# USB_Serial.net
KiCad netlist of a schematic drawn in Altium Designer
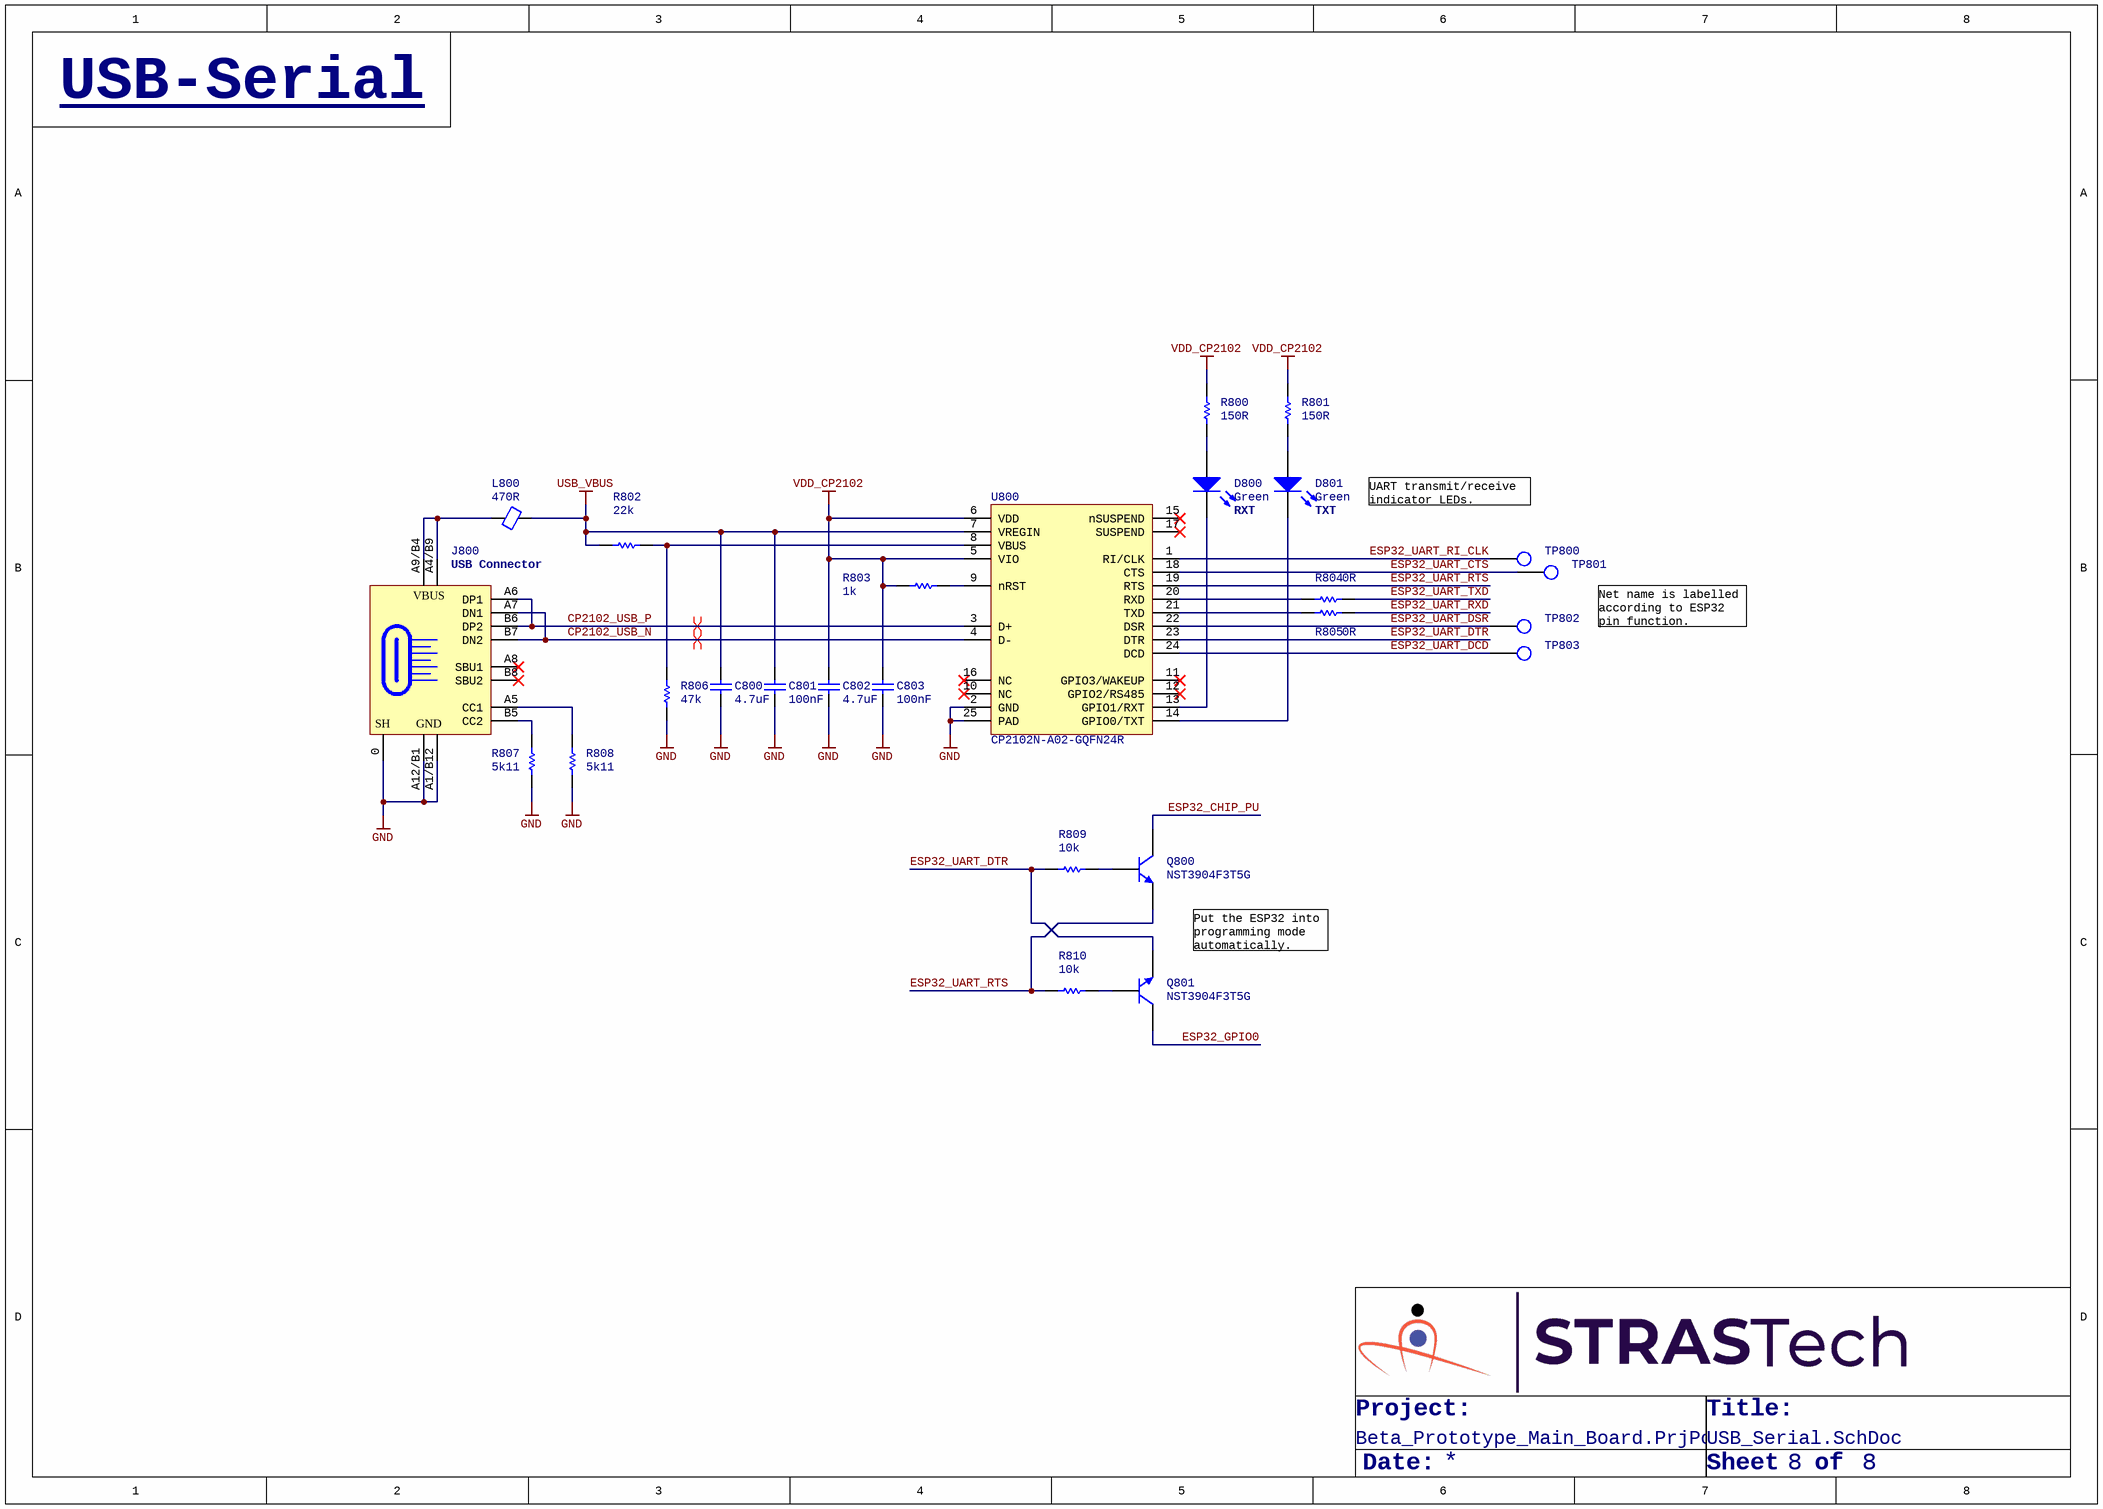
[diagram p0: USB_Serial.SchDoc]

(export (version "E")
  (design (tool "Eeschema 10.0.6"))
  (components
    (comp (ref "C800")
      (value "4.7uF")
      (footprint "Cap,SMD,0402")
      (description "4.7 µF ±20% 16V Ceramic Capacitor X5R 0402 (1005 Metric)")
      (fields
        (field (name "VENDOR PART NUMBER") "478-10788-1-ND")
        (field (name "MANUFACTURER") "AVX Corporation")
        (field (name "CREATEDBY") "Judd Foster")
      )
      (libsource (lib "symbols") (part "CAP,Cer,4.7uF,16VDC,X5R,0402"))
    )
    (comp (ref "C801")
      (value "100nF")
      (footprint "Cap,SMD,0402")
      (description "0.1µF ±10% 25V Ceramic Capacitor X7R 0402 (1005 Metric)")
      (fields
        (field (name "VENDOR PART NUMBER") "490-14603-1-ND")
        (field (name "MANUFACTURER") "Murata Electronics")
        (field (name "CREATEDBY") "Judd Foster")
      )
      (libsource (lib "symbols") (part "CAP,Cer,100nF,25VDC,X7R,0402"))
    )
    (comp (ref "C802")
      (value "4.7uF")
      (footprint "Cap,SMD,0402")
      (description "4.7 µF ±20% 16V Ceramic Capacitor X5R 0402 (1005 Metric)")
      (fields
        (field (name "VENDOR PART NUMBER") "478-10788-1-ND")
        (field (name "MANUFACTURER") "AVX Corporation")
        (field (name "CREATEDBY") "Judd Foster")
      )
      (libsource (lib "symbols") (part "CAP,Cer,4.7uF,16VDC,X5R,0402"))
    )
    (comp (ref "C803")
      (value "100nF")
      (footprint "Cap,SMD,0402")
      (description "0.1µF ±10% 25V Ceramic Capacitor X7R 0402 (1005 Metric)")
      (fields
        (field (name "VENDOR PART NUMBER") "490-14603-1-ND")
        (field (name "MANUFACTURER") "Murata Electronics")
        (field (name "CREATEDBY") "Judd Foster")
      )
      (libsource (lib "symbols") (part "CAP,Cer,100nF,25VDC,X7R,0402"))
    )
    (comp (ref "D800")
      (value "Green")
      (footprint "LED,0603")
      (description "Green 530nm LED Indication - Discrete 3V 0603 (1608 Metric)")
      (fields
        (field (name "MANUFACTURER") "Stanley Electric Co")
        (field (name "MANUFACTURER PART NUMBER") "THG1111C-0005-TR")
        (field (name "CREATEDBY") "Judd Foster")
      )
      (libsource (lib "symbols") (part "LED,Green,SMD,0603"))
    )
    (comp (ref "D801")
      (value "Green")
      (footprint "LED,0603")
      (description "Green 530nm LED Indication - Discrete 3V 0603 (1608 Metric)")
      (fields
        (field (name "MANUFACTURER") "Stanley Electric Co")
        (field (name "MANUFACTURER PART NUMBER") "THG1111C-0005-TR")
        (field (name "CREATEDBY") "Judd Foster")
      )
      (libsource (lib "symbols") (part "LED,Green,SMD,0603"))
    )
    (comp (ref "J800")
      (value "USB")
      (footprint "CONN,USB_C,SMD")
      (fields
        (field (name "MANUFACTURER") "GCT")
        (field (name "MANUFACTURER PART NUMBER") "USB4110-GF-A")
        (field (name "VENDOR PART NUMBER") "2073-USB4110-GF-A-1-ND")
        (field (name "CREATEDBY") "Judd Foster")
      )
      (libsource (lib "symbols") (part "Conn,USB_C,SMD"))
    )
    (comp (ref "L800")
      (value "470R")
      (footprint "IND,0402")
      (description "470 Ohms @ 100 MHz 1 Power Line Ferrite Bead 0402 (1005 Metric) 1A 200mOhm")
      (fields
        (field (name "VENDOR PART NUMBER") "490-10662-1-ND")
        (field (name "MANUFACTURER") "Murata Electronics")
        (field (name "CREATEDBY") "Judd Foster")
      )
      (libsource (lib "symbols") (part "Ferrite,470R@100MHz,0402"))
    )
    (comp (ref "Q800")
      (value "NST3904F3T5G")
      (footprint "SOT1123")
      (description "Bipolar (BJT) Transistor NPN 40 V 200 mA 200MHz 290 mW Surface Mount SOT-1123")
      (fields
        (field (name "MANUFACTURER") "ON Semiconductor")
        (field (name "VENDOR PART NUMBER") "NST3904F3T5GOSCT-ND")
        (field (name "CREATEDBY") "Judd Foster")
      )
      (libsource (lib "symbols") (part "Trans,NPN,40V,200mA,SOT1123"))
    )
    (comp (ref "Q801")
      (value "NST3904F3T5G")
      (footprint "SOT1123")
      (description "Bipolar (BJT) Transistor NPN 40 V 200 mA 200MHz 290 mW Surface Mount SOT-1123")
      (fields
        (field (name "MANUFACTURER") "ON Semiconductor")
        (field (name "VENDOR PART NUMBER") "NST3904F3T5GOSCT-ND")
        (field (name "CREATEDBY") "Judd Foster")
      )
      (libsource (lib "symbols") (part "Trans,NPN,40V,200mA,SOT1123"))
    )
    (comp (ref "R800")
      (value "150R")
      (footprint "RES,0402")
      (fields
        (field (name "MANUFACTURER") "TE Connectivity Passive Product")
        (field (name "MANUFACTURER PART NUMBER") "CRGCQ0402F150R")
        (field (name "VENDOR PART NUMBER") "A129617CT-ND")
        (field (name "CREATEDBY") "Judd Foster")
      )
      (libsource (lib "symbols") (part "RES,150R,1%,0.1W,0402"))
    )
    (comp (ref "R801")
      (value "150R")
      (footprint "RES,0402")
      (fields
        (field (name "MANUFACTURER") "TE Connectivity Passive Product")
        (field (name "MANUFACTURER PART NUMBER") "CRGCQ0402F150R")
        (field (name "VENDOR PART NUMBER") "A129617CT-ND")
        (field (name "CREATEDBY") "Judd Foster")
      )
      (libsource (lib "symbols") (part "RES,150R,1%,0.1W,0402"))
    )
    (comp (ref "R802")
      (value "22k")
      (footprint "RES,0402")
      (description "22 kOhms ±1% 0.063W, 1/16W Chip Resistor 0402 (1005 Metric) Automotive AEC-Q200 Thick Film")
      (fields
        (field (name "VENDOR PART NUMBER") "RMCF0402FT22K0CT-ND")
        (field (name "MANUFACTURER") "Stackpole Electronics Inc")
        (field (name "CREATEDBY") "Judd Foster")
      )
      (libsource (lib "symbols") (part "RES,22k,1%,0.063W,0402"))
    )
    (comp (ref "R803")
      (value "1k")
      (footprint "RES,0402")
      (description "1 kOhms ±5% 0.063W, 1/16W Chip Resistor 0402 (1005 Metric) Automotive AEC-Q200 Thick Film")
      (fields
        (field (name "VENDOR PART NUMBER") "RMCF0402JT1K00CT-ND")
        (field (name "MANUFACTURER") "Stackpole Electronics Inc")
        (field (name "CREATEDBY") "Judd Foster")
      )
      (libsource (lib "symbols") (part "RES,1k,5%,0.063W,0402"))
    )
    (comp (ref "R804")
      (value "0R")
      (footprint "RES,0402")
      (description "0 Ohms Jumper 0.1W, 1/10W Chip Resistor 0402 (1005 Metric) Automotive AEC-Q200 Thick Film")
      (fields
        (field (name "MANUFACTURER") "Panasonic Electronic Components")
        (field (name "MANUFACTURER PART NUMBER") "ERJ-2GE0R00X")
        (field (name "CREATEDBY") "Judd Foster")
      )
      (libsource (lib "symbols") (part "RES,0R0,0.1W,0402"))
    )
    (comp (ref "R805")
      (value "0R")
      (footprint "RES,0402")
      (description "0 Ohms Jumper 0.1W, 1/10W Chip Resistor 0402 (1005 Metric) Automotive AEC-Q200 Thick Film")
      (fields
        (field (name "MANUFACTURER") "Panasonic Electronic Components")
        (field (name "MANUFACTURER PART NUMBER") "ERJ-2GE0R00X")
        (field (name "CREATEDBY") "Judd Foster")
      )
      (libsource (lib "symbols") (part "RES,0R0,0.1W,0402"))
    )
    (comp (ref "R806")
      (value "47k")
      (footprint "RES,0402")
      (description "47 kOhms ±1% 0.1W, 1/10W Chip Resistor 0402 (1005 Metric) Automotive AEC-Q200 Thick Film")
      (fields
        (field (name "MANUFACTURER") "Panasonic Electronic Components")
        (field (name "MANUFACTURER PART NUMBER") "ERJ-2RKF4702X")
        (field (name "CREATEDBY") "Judd Foster")
      )
      (libsource (lib "symbols") (part "RES,47k,1%,0.1W,0402"))
    )
    (comp (ref "R807")
      (value "5k11")
      (footprint "RES,0402")
      (fields
        (field (name "MANUFACTURER") "Yageo")
        (field (name "MANUFACTURER PART NUMBER") "AC0402FR-075K11L")
        (field (name "VENDOR PART NUMBER") "13-AC0402FR-075K11LCT-ND")
        (field (name "CREATEDBY") "Judd Foster")
      )
      (libsource (lib "symbols") (part "RES,5k11,1%,0.063W,0402"))
    )
    (comp (ref "R808")
      (value "5k11")
      (footprint "RES,0402")
      (fields
        (field (name "MANUFACTURER") "Yageo")
        (field (name "MANUFACTURER PART NUMBER") "AC0402FR-075K11L")
        (field (name "VENDOR PART NUMBER") "13-AC0402FR-075K11LCT-ND")
        (field (name "CREATEDBY") "Judd Foster")
      )
      (libsource (lib "symbols") (part "RES,5k11,1%,0.063W,0402"))
    )
    (comp (ref "R809")
      (value "10k")
      (footprint "RES,0402")
      (description "10 kOhms ±5% 0.063W, 1/16W Chip Resistor 0402 (1005 Metric) Automotive AEC-Q200 Thick Film")
      (fields
        (field (name "VENDOR PART NUMBER") "RMCF0402JT10K0CT-ND")
        (field (name "MANUFACTURER") "Stackpole Electronics Inc")
        (field (name "CREATEDBY") "Judd Foster")
      )
      (libsource (lib "symbols") (part "RES,10k,5%,0.063W,0402"))
    )
    (comp (ref "R810")
      (value "10k")
      (footprint "RES,0402")
      (description "10 kOhms ±5% 0.063W, 1/16W Chip Resistor 0402 (1005 Metric) Automotive AEC-Q200 Thick Film")
      (fields
        (field (name "VENDOR PART NUMBER") "RMCF0402JT10K0CT-ND")
        (field (name "MANUFACTURER") "Stackpole Electronics Inc")
        (field (name "CREATEDBY") "Judd Foster")
      )
      (libsource (lib "symbols") (part "RES,10k,5%,0.063W,0402"))
    )
    (comp (ref "TP800")
      (value "TESTPOINT")
      (footprint "testpoint,smd,round,1mm")
      (description "PCB Testpoint")
      (fields (field (name "CREATEDBY") "Judd Foster"))
      (libsource (lib "symbols") (part "TESTPOINT"))
    )
    (comp (ref "TP801")
      (value "TESTPOINT")
      (footprint "testpoint,smd,round,1mm")
      (description "PCB Testpoint")
      (fields (field (name "CREATEDBY") "Judd Foster"))
      (libsource (lib "symbols") (part "TESTPOINT"))
    )
    (comp (ref "TP802")
      (value "TESTPOINT")
      (footprint "testpoint,smd,round,1mm")
      (description "PCB Testpoint")
      (fields (field (name "CREATEDBY") "Judd Foster"))
      (libsource (lib "symbols") (part "TESTPOINT"))
    )
    (comp (ref "TP803")
      (value "TESTPOINT")
      (footprint "testpoint,smd,round,1mm")
      (description "PCB Testpoint")
      (fields (field (name "CREATEDBY") "Judd Foster"))
      (libsource (lib "symbols") (part "TESTPOINT"))
    )
    (comp (ref "U800")
      (value "CP2102N-A02-GQFN24R")
      (footprint "IC,VQFN-24,THERMAL,4x4")
      (description "USB Bridge, USB to UART USB 2.0 UART Interface 24-QFN (4x4)")
      (fields
        (field (name "MANUFACTURER") "Silicon Labs")
        (field (name "VENDOR PART NUMBER") "336-5888-1-ND")
        (field (name "CREATEDBY") "Judd Foster")
      )
      (libsource (lib "symbols") (part "CP2102N-A02-GQFN24R"))
    )
  )
  (nets
    (net (code "1") (name "/CP2102_USB_N") (class "Default")
      (node (ref "J800") (pin "A7") (pinfunction "DN1_A7") (pintype "passive"))
      (node (ref "J800") (pin "B7") (pinfunction "DN2_B7") (pintype "passive"))
      (node (ref "U800") (pin "4") (pinfunction "D-_4") (pintype "passive"))
    )
    (net (code "2") (name "/CP2102_USB_P") (class "Default")
      (node (ref "J800") (pin "A6") (pinfunction "DP1_A6") (pintype "passive"))
      (node (ref "J800") (pin "B6") (pinfunction "DP2_B6") (pintype "passive"))
      (node (ref "U800") (pin "3") (pinfunction "D+_3") (pintype "passive"))
    )
    (net (code "3") (name "/ESP32_CHIP_PU") (class "Default")
      (node (ref "Q800") (pin "3") (pinfunction "C_3") (pintype "passive"))
    )
    (net (code "4") (name "/ESP32_GPIO0") (class "Default")
      (node (ref "Q801") (pin "3") (pinfunction "C_3") (pintype "passive"))
    )
    (net (code "5") (name "/ESP32_UART_CTS") (class "Default")
      (node (ref "TP801") (pin "1") (pinfunction "TP_1") (pintype "passive"))
      (node (ref "U800") (pin "18") (pinfunction "CTS_18") (pintype "passive"))
    )
    (net (code "6") (name "/ESP32_UART_DCD") (class "Default")
      (node (ref "TP803") (pin "1") (pinfunction "TP_1") (pintype "passive"))
      (node (ref "U800") (pin "24") (pinfunction "DCD_24") (pintype "passive"))
    )
    (net (code "7") (name "/ESP32_UART_DSR") (class "Default")
      (node (ref "TP802") (pin "1") (pinfunction "TP_1") (pintype "passive"))
      (node (ref "U800") (pin "22") (pinfunction "DSR_22") (pintype "passive"))
    )
    (net (code "8") (name "/ESP32_UART_DTR") (class "Default")
      (node (ref "Q801") (pin "2") (pinfunction "E_2") (pintype "passive"))
      (node (ref "R809") (pin "2") (pinfunction "2_2") (pintype "passive"))
      (node (ref "U800") (pin "23") (pinfunction "DTR_23") (pintype "passive"))
    )
    (net (code "9") (name "/ESP32_UART_RI_CLK") (class "Default")
      (node (ref "TP800") (pin "1") (pinfunction "TP_1") (pintype "passive"))
      (node (ref "U800") (pin "1") (pinfunction "RI/CLK_1") (pintype "passive"))
    )
    (net (code "10") (name "/ESP32_UART_RTS") (class "Default")
      (node (ref "Q800") (pin "2") (pinfunction "E_2") (pintype "passive"))
      (node (ref "R810") (pin "2") (pinfunction "2_2") (pintype "passive"))
      (node (ref "U800") (pin "19") (pinfunction "RTS_19") (pintype "passive"))
    )
    (net (code "11") (name "/ESP32_UART_RXD") (class "Default")
      (node (ref "R805") (pin "2") (pinfunction "2_2") (pintype "passive"))
    )
    (net (code "12") (name "/ESP32_UART_TXD") (class "Default")
      (node (ref "R804") (pin "2") (pinfunction "2_2") (pintype "passive"))
    )
    (net (code "13") (name "GND") (class "Default")
      (node (ref "C800") (pin "1") (pinfunction "1_1") (pintype "passive"))
      (node (ref "C801") (pin "1") (pinfunction "1_1") (pintype "passive"))
      (node (ref "C802") (pin "1") (pinfunction "1_1") (pintype "passive"))
      (node (ref "C803") (pin "1") (pinfunction "1_1") (pintype "passive"))
      (node (ref "J800") (pin "0") (pinfunction "SHIELD_0") (pintype "passive"))
      (node (ref "J800") (pin "A1/B12") (pinfunction "GND_A1/B12") (pintype "passive"))
      (node (ref "J800") (pin "A12/B1") (pinfunction "GND_A12/B1") (pintype "passive"))
      (node (ref "R806") (pin "1") (pinfunction "1_1") (pintype "passive"))
      (node (ref "R807") (pin "1") (pinfunction "1_1") (pintype "passive"))
      (node (ref "R808") (pin "1") (pinfunction "1_1") (pintype "passive"))
      (node (ref "U800") (pin "2") (pinfunction "GND_2") (pintype "passive"))
      (node (ref "U800") (pin "25") (pinfunction "PAD_25") (pintype "passive"))
    )
    (net (code "14") (name "Net-(D800-A)") (class "Default")
      (node (ref "D800") (pin "1") (pinfunction "A_1") (pintype "passive"))
      (node (ref "R800") (pin "1") (pinfunction "1_1") (pintype "passive"))
    )
    (net (code "15") (name "Net-(D800-K)") (class "Default")
      (node (ref "D800") (pin "2") (pinfunction "K_2") (pintype "passive"))
      (node (ref "U800") (pin "13") (pinfunction "GPIO1/RXT_13") (pintype "passive"))
    )
    (net (code "16") (name "Net-(D801-A)") (class "Default")
      (node (ref "D801") (pin "1") (pinfunction "A_1") (pintype "passive"))
      (node (ref "R801") (pin "1") (pinfunction "1_1") (pintype "passive"))
    )
    (net (code "17") (name "Net-(D801-K)") (class "Default")
      (node (ref "D801") (pin "2") (pinfunction "K_2") (pintype "passive"))
      (node (ref "U800") (pin "14") (pinfunction "GPIO0/TXT_14") (pintype "passive"))
    )
    (net (code "18") (name "Net-(J800-CC1)") (class "Default")
      (node (ref "J800") (pin "A5") (pinfunction "CC1_A5") (pintype "passive"))
      (node (ref "R808") (pin "2") (pinfunction "2_2") (pintype "passive"))
    )
    (net (code "19") (name "Net-(J800-CC2)") (class "Default")
      (node (ref "J800") (pin "B5") (pinfunction "CC2_B5") (pintype "passive"))
      (node (ref "R807") (pin "2") (pinfunction "2_2") (pintype "passive"))
    )
    (net (code "20") (name "Net-(J800-VBUS-PadA4{slash}B9)") (class "Default")
      (node (ref "J800") (pin "A4/B9") (pinfunction "VBUS_A4/B9") (pintype "passive"))
      (node (ref "J800") (pin "A9/B4") (pinfunction "VBUS_A9/B4") (pintype "passive"))
      (node (ref "L800") (pin "1") (pinfunction "1_1") (pintype "passive"))
    )
    (net (code "21") (name "Net-(Q800-B)") (class "Default")
      (node (ref "Q800") (pin "1") (pinfunction "B_1") (pintype "passive"))
      (node (ref "R809") (pin "1") (pinfunction "1_1") (pintype "passive"))
    )
    (net (code "22") (name "Net-(Q801-B)") (class "Default")
      (node (ref "Q801") (pin "1") (pinfunction "B_1") (pintype "passive"))
      (node (ref "R810") (pin "1") (pinfunction "1_1") (pintype "passive"))
    )
    (net (code "23") (name "Net-(U800-RXD)") (class "Default")
      (node (ref "R804") (pin "1") (pinfunction "1_1") (pintype "passive"))
      (node (ref "U800") (pin "20") (pinfunction "RXD_20") (pintype "passive"))
    )
    (net (code "24") (name "Net-(U800-TXD)") (class "Default")
      (node (ref "R805") (pin "1") (pinfunction "1_1") (pintype "passive"))
      (node (ref "U800") (pin "21") (pinfunction "TXD_21") (pintype "passive"))
    )
    (net (code "25") (name "Net-(U800-VBUS)") (class "Default")
      (node (ref "R802") (pin "2") (pinfunction "2_2") (pintype "passive"))
      (node (ref "R806") (pin "2") (pinfunction "2_2") (pintype "passive"))
      (node (ref "U800") (pin "8") (pinfunction "VBUS_8") (pintype "passive"))
    )
    (net (code "26") (name "Net-(U800-nRST)") (class "Default")
      (node (ref "R803") (pin "1") (pinfunction "1_1") (pintype "passive"))
      (node (ref "U800") (pin "9") (pinfunction "nRST_9") (pintype "passive"))
    )
    (net (code "27") (name "USB_VBUS") (class "Default")
      (node (ref "C800") (pin "2") (pinfunction "2_2") (pintype "passive"))
      (node (ref "C801") (pin "2") (pinfunction "2_2") (pintype "passive"))
      (node (ref "L800") (pin "2") (pinfunction "2_2") (pintype "passive"))
      (node (ref "R802") (pin "1") (pinfunction "1_1") (pintype "passive"))
      (node (ref "U800") (pin "7") (pinfunction "VREGIN_7") (pintype "passive"))
    )
    (net (code "28") (name "VDD_CP2102") (class "Default")
      (node (ref "C802") (pin "2") (pinfunction "2_2") (pintype "passive"))
      (node (ref "C803") (pin "2") (pinfunction "2_2") (pintype "passive"))
      (node (ref "R800") (pin "2") (pinfunction "2_2") (pintype "passive"))
      (node (ref "R801") (pin "2") (pinfunction "2_2") (pintype "passive"))
      (node (ref "R803") (pin "2") (pinfunction "2_2") (pintype "passive"))
      (node (ref "U800") (pin "5") (pinfunction "VIO_5") (pintype "passive"))
      (node (ref "U800") (pin "6") (pinfunction "VDD_6") (pintype "passive"))
    )
    (net (code "29") (name "unconnected-(J800-SBU1-PadA8)") (class "Default")
      (node (ref "J800") (pin "A8") (pinfunction "SBU1_A8") (pintype "passive+no_connect"))
    )
    (net (code "30") (name "unconnected-(J800-SBU2-PadB8)") (class "Default")
      (node (ref "J800") (pin "B8") (pinfunction "SBU2_B8") (pintype "passive+no_connect"))
    )
    (net (code "31") (name "unconnected-(U800-GPIO2{slash}RS485-Pad12)") (class "Default")
      (node (ref "U800") (pin "12") (pinfunction "GPIO2/RS485_12") (pintype "passive+no_connect"))
    )
    (net (code "32") (name "unconnected-(U800-GPIO3{slash}WAKEUP-Pad11)") (class "Default")
      (node (ref "U800") (pin "11") (pinfunction "GPIO3/WAKEUP_11") (pintype "passive+no_connect"))
    )
    (net (code "33") (name "unconnected-(U800-NC-Pad10)") (class "Default")
      (node (ref "U800") (pin "10") (pinfunction "NC_10") (pintype "passive+no_connect"))
    )
    (net (code "34") (name "unconnected-(U800-NC-Pad16)") (class "Default")
      (node (ref "U800") (pin "16") (pinfunction "NC_16") (pintype "passive+no_connect"))
    )
    (net (code "35") (name "unconnected-(U800-SUSPEND-Pad17)") (class "Default")
      (node (ref "U800") (pin "17") (pinfunction "SUSPEND_17") (pintype "passive+no_connect"))
    )
    (net (code "36") (name "unconnected-(U800-nSUSPEND-Pad15)") (class "Default")
      (node (ref "U800") (pin "15") (pinfunction "nSUSPEND_15") (pintype "passive+no_connect"))
    )
  )
)
